# Audio.net
KiCad netlist of a schematic drawn in Altium Designer
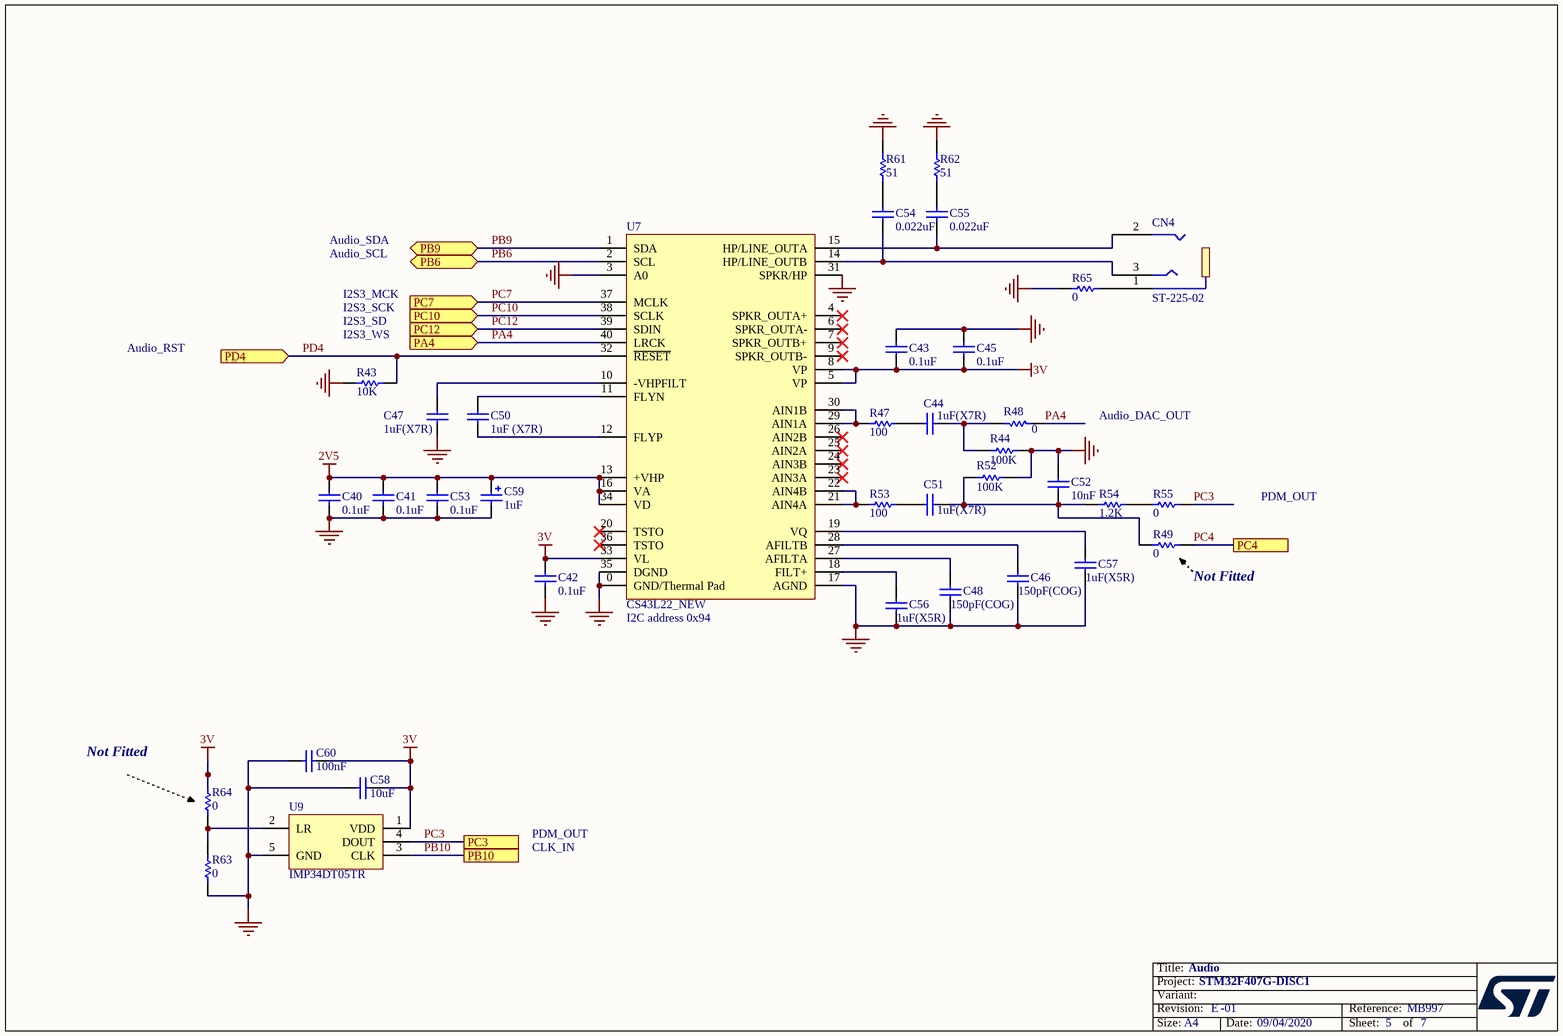
[diagram p0: Audio.SchDoc]

(export (version "E")
  (design (tool "Eeschema 10.0.6"))
  (components
    (comp (ref "C40")
      (value "0.1uF")
      (footprint "0402C")
      (description "Capacitor")
      (fields (field (name "PUBLISHER") "Altium Limited"))
      (libsource (lib "Miscellaneous Devices") (part "CAP"))
    )
    (comp (ref "C41")
      (value "0.1uF")
      (footprint "0402C")
      (description "Capacitor")
      (fields (field (name "PUBLISHER") "Altium Limited"))
      (libsource (lib "Miscellaneous Devices") (part "CAP"))
    )
    (comp (ref "C42")
      (value "0.1uF")
      (footprint "0402C")
      (description "Capacitor")
      (fields (field (name "PUBLISHER") "Altium Limited"))
      (libsource (lib "Miscellaneous Devices") (part "CAP"))
    )
    (comp (ref "C43")
      (value "0.1uF")
      (footprint "0402C")
      (description "Capacitor")
      (fields (field (name "PUBLISHER") "Altium Limited"))
      (libsource (lib "Miscellaneous Devices") (part "CAP"))
    )
    (comp (ref "C44")
      (value "1uF(X7R)")
      (footprint "0603C")
      (description "Capacitor")
      (fields (field (name "PUBLISHER") "Altium Limited"))
      (libsource (lib "Miscellaneous Devices") (part "CAP"))
    )
    (comp (ref "C45")
      (value "0.1uF")
      (footprint "0402C")
      (description "Capacitor")
      (fields (field (name "PUBLISHER") "Altium Limited"))
      (libsource (lib "Miscellaneous Devices") (part "CAP"))
    )
    (comp (ref "C46")
      (value "150pF(COG)")
      (footprint "0603C")
      (description "Capacitor")
      (fields (field (name "PUBLISHER") "Altium Limited"))
      (libsource (lib "Miscellaneous Devices") (part "CAP"))
    )
    (comp (ref "C47")
      (value "1uF(X7R)")
      (footprint "0603C")
      (description "Capacitor")
      (fields (field (name "PUBLISHER") "Altium Limited"))
      (libsource (lib "Miscellaneous Devices") (part "CAP"))
    )
    (comp (ref "C48")
      (value "150pF(COG)")
      (footprint "0603C")
      (description "Capacitor")
      (fields (field (name "PUBLISHER") "Altium Limited"))
      (libsource (lib "Miscellaneous Devices") (part "CAP"))
    )
    (comp (ref "C50")
      (value "1uF (X7R)")
      (footprint "0603C")
      (description "Capacitor")
      (fields (field (name "PUBLISHER") "Altium Limited"))
      (libsource (lib "Miscellaneous Devices") (part "CAP"))
    )
    (comp (ref "C51")
      (value "1uF(X7R)")
      (footprint "0603C")
      (description "Capacitor")
      (fields (field (name "PUBLISHER") "Altium Limited"))
      (libsource (lib "Miscellaneous Devices") (part "CAP"))
    )
    (comp (ref "C52")
      (value "10nF")
      (footprint "0603C")
      (description "Capacitor")
      (fields (field (name "PUBLISHER") "Altium Limited"))
      (libsource (lib "Miscellaneous Devices") (part "CAP"))
    )
    (comp (ref "C53")
      (value "0.1uF")
      (footprint "0402C")
      (description "Capacitor")
      (fields (field (name "PUBLISHER") "Altium Limited"))
      (libsource (lib "Miscellaneous Devices") (part "CAP"))
    )
    (comp (ref "C54")
      (value "0.022uF")
      (footprint "0603C")
      (description "Capacitor")
      (fields (field (name "PUBLISHER") "Altium Limited"))
      (libsource (lib "Miscellaneous Devices") (part "CAP"))
    )
    (comp (ref "C55")
      (value "0.022uF")
      (footprint "0603C")
      (description "Capacitor")
      (fields (field (name "PUBLISHER") "Altium Limited"))
      (libsource (lib "Miscellaneous Devices") (part "CAP"))
    )
    (comp (ref "C56")
      (value "1uF(X5R)")
      (footprint "0603C")
      (description "Capacitor")
      (fields (field (name "PUBLISHER") "Altium Limited"))
      (libsource (lib "Miscellaneous Devices") (part "CAP"))
    )
    (comp (ref "C57")
      (value "1uF(X5R)")
      (footprint "0603C")
      (description "Capacitor")
      (fields (field (name "PUBLISHER") "Altium Limited"))
      (libsource (lib "Miscellaneous Devices") (part "CAP"))
    )
    (comp (ref "C58")
      (value "10uF")
      (footprint "0603C")
      (description "Capacitor")
      (fields (field (name "PUBLISHER") "Altium Limited"))
      (libsource (lib "Miscellaneous Devices") (part "CAP"))
    )
    (comp (ref "C59")
      (value "1uF")
      (footprint "CASE-A")
      (description "Polarized Capacitor (Radial)")
      (fields (field (name "PUBLISHER") "Altium Limited"))
      (libsource (lib "Miscellaneous Devices") (part "Cap Pol1"))
    )
    (comp (ref "C60")
      (value "100nF")
      (footprint "0402C")
      (description "Capacitor")
      (fields (field (name "PUBLISHER") "Altium Limited"))
      (libsource (lib "Miscellaneous Devices") (part "CAP"))
    )
    (comp (ref "CN4")
      (value "ST-225-02")
      (footprint "PCBCOMPONENT_1$2F$2_new_")
      (description "Connector Jack 35mm")
      (libsource (lib "MB997") (part "ST-225-02_"))
    )
    (comp (ref "R43")
      (value "10K")
      (footprint "0402R")
      (description "Resistor")
      (fields (field (name "PUBLISHER") "Altium Limited"))
      (libsource (lib "Miscellaneous Devices") (part "res1"))
    )
    (comp (ref "R44")
      (value "100K")
      (footprint "0402R")
      (description "Resistor")
      (fields (field (name "PUBLISHER") "Altium Limited"))
      (libsource (lib "Miscellaneous Devices") (part "res1"))
    )
    (comp (ref "R47")
      (value "100")
      (footprint "0402R")
      (description "Resistor")
      (fields (field (name "PUBLISHER") "Altium Limited"))
      (libsource (lib "Miscellaneous Devices") (part "res1"))
    )
    (comp (ref "R48")
      (value "0")
      (footprint "0603R")
      (description "Resistor")
      (fields (field (name "PUBLISHER") "Altium Limited"))
      (libsource (lib "Miscellaneous Devices") (part "res1"))
    )
    (comp (ref "R49")
      (value "0")
      (footprint "0603R")
      (description "Resistor")
      (fields (field (name "PUBLISHER") "Altium Limited"))
      (libsource (lib "Miscellaneous Devices") (part "res1"))
    )
    (comp (ref "R52")
      (value "100K")
      (footprint "0402R")
      (description "Resistor")
      (fields (field (name "PUBLISHER") "Altium Limited"))
      (libsource (lib "Miscellaneous Devices") (part "res1"))
    )
    (comp (ref "R53")
      (value "100")
      (footprint "0402R")
      (description "Resistor")
      (fields (field (name "PUBLISHER") "Altium Limited"))
      (libsource (lib "Miscellaneous Devices") (part "res1"))
    )
    (comp (ref "R54")
      (value "1.2K")
      (footprint "0603R")
      (description "Resistor")
      (fields (field (name "PUBLISHER") "Altium Limited"))
      (libsource (lib "Miscellaneous Devices") (part "res1"))
    )
    (comp (ref "R55")
      (value "0")
      (footprint "0603R")
      (description "Resistor")
      (fields (field (name "PUBLISHER") "Altium Limited"))
      (libsource (lib "Miscellaneous Devices") (part "res1"))
    )
    (comp (ref "R61")
      (value "51")
      (footprint "0603R")
      (description "Resistor")
      (fields (field (name "PUBLISHER") "Altium Limited"))
      (libsource (lib "Miscellaneous Devices") (part "res1"))
    )
    (comp (ref "R62")
      (value "51")
      (footprint "0603R")
      (description "Resistor")
      (fields (field (name "PUBLISHER") "Altium Limited"))
      (libsource (lib "Miscellaneous Devices") (part "res1"))
    )
    (comp (ref "R63")
      (value "0")
      (footprint "0402R")
      (description "Resistor")
      (fields (field (name "PUBLISHER") "Altium Limited"))
      (libsource (lib "Miscellaneous Devices") (part "res1"))
    )
    (comp (ref "R64")
      (value "0")
      (footprint "0402R")
      (description "Resistor")
      (fields (field (name "PUBLISHER") "Altium Limited"))
      (libsource (lib "Miscellaneous Devices") (part "res1"))
    )
    (comp (ref "R65")
      (value "0")
      (footprint "0603R")
      (description "Resistor")
      (fields (field (name "PUBLISHER") "Altium Limited"))
      (libsource (lib "Miscellaneous Devices") (part "res1"))
    )
    (comp (ref "U7")
      (value "CS43L22_NEW")
      (footprint "QFN40(6_6)")
      (description "Low Power, Stereo DAC w/Headphone & Speaker Amps")
      (libsource (lib "MB997") (part "CS43L22_NEW"))
    )
    (comp (ref "U9")
      (value "IMP34DT05TR")
      (footprint "MIC_HCLGA_3X4X1_4LD_t")
      (description "MEMS audio sensor omnidirectional digital microphone for industrial applications")
      (libsource (lib "MB997") (part "IMP34DT05TR"))
    )
  )
  (nets
    (net (code "1") (name "/PA4") (class "Default")
      (node (ref "R48") (pin "2") (pinfunction "2_2") (pintype "passive"))
      (node (ref "U7") (pin "40") (pinfunction "LRCK_40") (pintype "passive"))
    )
    (net (code "2") (name "/PB6") (class "Default")
      (node (ref "U7") (pin "2") (pinfunction "SCL_2") (pintype "passive"))
    )
    (net (code "3") (name "/PB9") (class "Default")
      (node (ref "U7") (pin "1") (pinfunction "SDA_1") (pintype "passive"))
    )
    (net (code "4") (name "/PB10") (class "Default")
      (node (ref "U9") (pin "3") (pinfunction "CLK_3") (pintype "passive"))
    )
    (net (code "5") (name "/PC3") (class "Default")
      (node (ref "R55") (pin "1") (pinfunction "1_1") (pintype "passive"))
      (node (ref "U9") (pin "4") (pinfunction "DOUT_4") (pintype "passive"))
    )
    (net (code "6") (name "/PC4") (class "Default")
      (node (ref "R49") (pin "1") (pinfunction "1_1") (pintype "passive"))
    )
    (net (code "7") (name "/PC7") (class "Default")
      (node (ref "U7") (pin "37") (pinfunction "MCLK_37") (pintype "passive"))
    )
    (net (code "8") (name "/PC10") (class "Default")
      (node (ref "U7") (pin "38") (pinfunction "SCLK_38") (pintype "passive"))
    )
    (net (code "9") (name "/PC12") (class "Default")
      (node (ref "U7") (pin "39") (pinfunction "SDIN_39") (pintype "passive"))
    )
    (net (code "10") (name "/PD4") (class "Default")
      (node (ref "R43") (pin "1") (pinfunction "1_1") (pintype "passive"))
      (node (ref "U7") (pin "32") (pinfunction "~{RESET}_32") (pintype "passive"))
    )
    (net (code "11") (name "2V5") (class "Default")
      (node (ref "C40") (pin "2") (pinfunction "2_2") (pintype "passive"))
      (node (ref "C41") (pin "2") (pinfunction "2_2") (pintype "passive"))
      (node (ref "C53") (pin "2") (pinfunction "2_2") (pintype "passive"))
      (node (ref "C59") (pin "1") (pinfunction "1_1") (pintype "passive"))
      (node (ref "U7") (pin "13") (pinfunction "+VHP_13") (pintype "passive"))
      (node (ref "U7") (pin "16") (pinfunction "VA_16") (pintype "passive"))
      (node (ref "U7") (pin "34") (pinfunction "VD_34") (pintype "passive"))
    )
    (net (code "12") (name "3V") (class "Default")
      (node (ref "C42") (pin "2") (pinfunction "2_2") (pintype "passive"))
      (node (ref "C43") (pin "2") (pinfunction "2_2") (pintype "passive"))
      (node (ref "C45") (pin "2") (pinfunction "2_2") (pintype "passive"))
      (node (ref "C58") (pin "2") (pinfunction "2_2") (pintype "passive"))
      (node (ref "C60") (pin "2") (pinfunction "2_2") (pintype "passive"))
      (node (ref "R64") (pin "2") (pinfunction "2_2") (pintype "passive"))
      (node (ref "U7") (pin "33") (pinfunction "VL_33") (pintype "passive"))
      (node (ref "U7") (pin "5") (pinfunction "VP_5") (pintype "passive"))
      (node (ref "U7") (pin "8") (pinfunction "VP_8") (pintype "passive"))
      (node (ref "U9") (pin "1") (pinfunction "VDD_1") (pintype "power_in"))
    )
    (net (code "13") (name "GND") (class "Default")
      (node (ref "C40") (pin "1") (pinfunction "1_1") (pintype "passive"))
      (node (ref "C41") (pin "1") (pinfunction "1_1") (pintype "passive"))
      (node (ref "C42") (pin "1") (pinfunction "1_1") (pintype "passive"))
      (node (ref "C43") (pin "1") (pinfunction "1_1") (pintype "passive"))
      (node (ref "C45") (pin "1") (pinfunction "1_1") (pintype "passive"))
      (node (ref "C46") (pin "1") (pinfunction "1_1") (pintype "passive"))
      (node (ref "C47") (pin "2") (pinfunction "2_2") (pintype "passive"))
      (node (ref "C48") (pin "1") (pinfunction "1_1") (pintype "passive"))
      (node (ref "C52") (pin "2") (pinfunction "2_2") (pintype "passive"))
      (node (ref "C53") (pin "1") (pinfunction "1_1") (pintype "passive"))
      (node (ref "C56") (pin "1") (pinfunction "1_1") (pintype "passive"))
      (node (ref "C57") (pin "1") (pinfunction "1_1") (pintype "passive"))
      (node (ref "C58") (pin "1") (pinfunction "1_1") (pintype "passive"))
      (node (ref "C59") (pin "2") (pinfunction "2_2") (pintype "passive"))
      (node (ref "C60") (pin "1") (pinfunction "1_1") (pintype "passive"))
      (node (ref "R43") (pin "2") (pinfunction "2_2") (pintype "passive"))
      (node (ref "R44") (pin "2") (pinfunction "2_2") (pintype "passive"))
      (node (ref "R52") (pin "2") (pinfunction "2_2") (pintype "passive"))
      (node (ref "R61") (pin "1") (pinfunction "1_1") (pintype "passive"))
      (node (ref "R62") (pin "1") (pinfunction "1_1") (pintype "passive"))
      (node (ref "R63") (pin "1") (pinfunction "1_1") (pintype "passive"))
      (node (ref "R65") (pin "2") (pinfunction "2_2") (pintype "passive"))
      (node (ref "U7") (pin "0") (pinfunction "GND/Thermal_Pad_0") (pintype "passive"))
      (node (ref "U7") (pin "17") (pinfunction "AGND_17") (pintype "passive"))
      (node (ref "U7") (pin "3") (pinfunction "A0_3") (pintype "passive"))
      (node (ref "U7") (pin "31") (pinfunction "SPKR/HP_31") (pintype "passive"))
      (node (ref "U7") (pin "35") (pinfunction "DGND_35") (pintype "passive"))
      (node (ref "U9") (pin "5") (pinfunction "GND_5") (pintype "passive"))
    )
    (net (code "14") (name "Net-(C44-Pad1)") (class "Default")
      (node (ref "C44") (pin "1") (pinfunction "1_1") (pintype "passive"))
      (node (ref "R47") (pin "1") (pinfunction "1_1") (pintype "passive"))
    )
    (net (code "15") (name "Net-(C44-Pad2)") (class "Default")
      (node (ref "C44") (pin "2") (pinfunction "2_2") (pintype "passive"))
      (node (ref "R44") (pin "1") (pinfunction "1_1") (pintype "passive"))
      (node (ref "R48") (pin "1") (pinfunction "1_1") (pintype "passive"))
    )
    (net (code "16") (name "Net-(C51-Pad1)") (class "Default")
      (node (ref "C51") (pin "1") (pinfunction "1_1") (pintype "passive"))
      (node (ref "R53") (pin "1") (pinfunction "1_1") (pintype "passive"))
    )
    (net (code "17") (name "Net-(C51-Pad2)") (class "Default")
      (node (ref "C51") (pin "2") (pinfunction "2_2") (pintype "passive"))
      (node (ref "C52") (pin "1") (pinfunction "1_1") (pintype "passive"))
      (node (ref "R49") (pin "2") (pinfunction "2_2") (pintype "passive"))
      (node (ref "R52") (pin "1") (pinfunction "1_1") (pintype "passive"))
      (node (ref "R54") (pin "1") (pinfunction "1_1") (pintype "passive"))
    )
    (net (code "18") (name "Net-(C54-Pad1)") (class "Default")
      (node (ref "C54") (pin "1") (pinfunction "1_1") (pintype "passive"))
      (node (ref "R61") (pin "2") (pinfunction "2_2") (pintype "passive"))
    )
    (net (code "19") (name "Net-(C55-Pad1)") (class "Default")
      (node (ref "C55") (pin "1") (pinfunction "1_1") (pintype "passive"))
      (node (ref "R62") (pin "2") (pinfunction "2_2") (pintype "passive"))
    )
    (net (code "20") (name "Net-(CN4-Pad1)") (class "Default")
      (node (ref "CN4") (pin "1") (pintype "passive"))
      (node (ref "R65") (pin "1") (pinfunction "1_1") (pintype "passive"))
    )
    (net (code "21") (name "Net-(R54-Pad2)") (class "Default")
      (node (ref "R54") (pin "2") (pinfunction "2_2") (pintype "passive"))
      (node (ref "R55") (pin "2") (pinfunction "2_2") (pintype "passive"))
    )
    (net (code "22") (name "Net-(U7--VHPFILT)") (class "Default")
      (node (ref "C47") (pin "1") (pinfunction "1_1") (pintype "passive"))
      (node (ref "U7") (pin "10") (pinfunction "-VHPFILT_10") (pintype "passive"))
    )
    (net (code "23") (name "Net-(U7-AFILTA)") (class "Default")
      (node (ref "C48") (pin "2") (pinfunction "2_2") (pintype "passive"))
      (node (ref "U7") (pin "27") (pinfunction "AFILTA_27") (pintype "passive"))
    )
    (net (code "24") (name "Net-(U7-AFILTB)") (class "Default")
      (node (ref "C46") (pin "2") (pinfunction "2_2") (pintype "passive"))
      (node (ref "U7") (pin "28") (pinfunction "AFILTB_28") (pintype "passive"))
    )
    (net (code "25") (name "Net-(U7-AIN1A)") (class "Default")
      (node (ref "R47") (pin "2") (pinfunction "2_2") (pintype "passive"))
      (node (ref "U7") (pin "29") (pinfunction "AIN1A_29") (pintype "passive"))
      (node (ref "U7") (pin "30") (pinfunction "AIN1B_30") (pintype "passive"))
    )
    (net (code "26") (name "Net-(U7-AIN4A)") (class "Default")
      (node (ref "R53") (pin "2") (pinfunction "2_2") (pintype "passive"))
      (node (ref "U7") (pin "21") (pinfunction "AIN4A_21") (pintype "passive"))
      (node (ref "U7") (pin "22") (pinfunction "AIN4B_22") (pintype "passive"))
    )
    (net (code "27") (name "Net-(U7-FILT+)") (class "Default")
      (node (ref "C56") (pin "2") (pinfunction "2_2") (pintype "passive"))
      (node (ref "U7") (pin "18") (pinfunction "FILT+_18") (pintype "passive"))
    )
    (net (code "28") (name "Net-(U7-FLYN)") (class "Default")
      (node (ref "C50") (pin "2") (pinfunction "2_2") (pintype "passive"))
      (node (ref "U7") (pin "11") (pinfunction "FLYN_11") (pintype "passive"))
    )
    (net (code "29") (name "Net-(U7-FLYP)") (class "Default")
      (node (ref "C50") (pin "1") (pinfunction "1_1") (pintype "passive"))
      (node (ref "U7") (pin "12") (pinfunction "FLYP_12") (pintype "passive"))
    )
    (net (code "30") (name "Net-(U7-HP{slash}LINE_OUTA)") (class "Default")
      (node (ref "C55") (pin "2") (pinfunction "2_2") (pintype "passive"))
      (node (ref "CN4") (pin "2") (pintype "passive"))
      (node (ref "U7") (pin "15") (pinfunction "HP/LINE_OUTA_15") (pintype "passive"))
    )
    (net (code "31") (name "Net-(U7-HP{slash}LINE_OUTB)") (class "Default")
      (node (ref "C54") (pin "2") (pinfunction "2_2") (pintype "passive"))
      (node (ref "CN4") (pin "3") (pintype "passive"))
      (node (ref "U7") (pin "14") (pinfunction "HP/LINE_OUTB_14") (pintype "passive"))
    )
    (net (code "32") (name "Net-(U7-VQ)") (class "Default")
      (node (ref "C57") (pin "2") (pinfunction "2_2") (pintype "passive"))
      (node (ref "U7") (pin "19") (pinfunction "VQ_19") (pintype "passive"))
    )
    (net (code "33") (name "Net-(U9-LR)") (class "Default")
      (node (ref "R63") (pin "2") (pinfunction "2_2") (pintype "passive"))
      (node (ref "R64") (pin "1") (pinfunction "1_1") (pintype "passive"))
      (node (ref "U9") (pin "2") (pinfunction "LR_2") (pintype "passive"))
    )
    (net (code "34") (name "unconnected-(U7-AIN2A-Pad25)") (class "Default")
      (node (ref "U7") (pin "25") (pinfunction "AIN2A_25") (pintype "passive+no_connect"))
    )
    (net (code "35") (name "unconnected-(U7-AIN2B-Pad26)") (class "Default")
      (node (ref "U7") (pin "26") (pinfunction "AIN2B_26") (pintype "passive+no_connect"))
    )
    (net (code "36") (name "unconnected-(U7-AIN3A-Pad23)") (class "Default")
      (node (ref "U7") (pin "23") (pinfunction "AIN3A_23") (pintype "passive+no_connect"))
    )
    (net (code "37") (name "unconnected-(U7-AIN3B-Pad24)") (class "Default")
      (node (ref "U7") (pin "24") (pinfunction "AIN3B_24") (pintype "passive+no_connect"))
    )
    (net (code "38") (name "unconnected-(U7-SPKR_OUTA+-Pad4)") (class "Default")
      (node (ref "U7") (pin "4") (pinfunction "SPKR_OUTA+_4") (pintype "passive+no_connect"))
    )
    (net (code "39") (name "unconnected-(U7-SPKR_OUTA--Pad6)") (class "Default")
      (node (ref "U7") (pin "6") (pinfunction "SPKR_OUTA-_6") (pintype "passive+no_connect"))
    )
    (net (code "40") (name "unconnected-(U7-SPKR_OUTB+-Pad7)") (class "Default")
      (node (ref "U7") (pin "7") (pinfunction "SPKR_OUTB+_7") (pintype "passive+no_connect"))
    )
    (net (code "41") (name "unconnected-(U7-SPKR_OUTB--Pad9)") (class "Default")
      (node (ref "U7") (pin "9") (pinfunction "SPKR_OUTB-_9") (pintype "passive+no_connect"))
    )
    (net (code "42") (name "unconnected-(U7-TSTO-Pad20)") (class "Default")
      (node (ref "U7") (pin "20") (pinfunction "TSTO_20") (pintype "passive+no_connect"))
    )
    (net (code "43") (name "unconnected-(U7-TSTO-Pad36)") (class "Default")
      (node (ref "U7") (pin "36") (pinfunction "TSTO_36") (pintype "passive+no_connect"))
    )
  )
)
